# RC522.net
KiCad netlist of a schematic drawn in Altium Designer
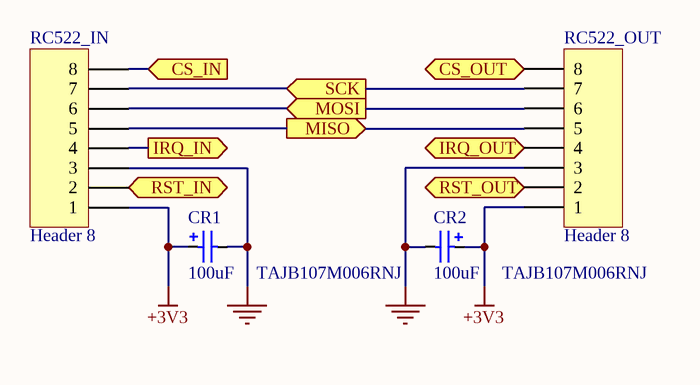
[diagram p0: RC522.SchDoc]

(export (version "E")
  (design (tool "Eeschema 10.0.6"))
  (components
    (comp (ref "CR1")
      (value "100uF     TAJB107M006RNJ")
      (footprint "CAP_TAN_B_3518")
      (description "Capacitor")
      (fields (field (name "Comment") "Cap_Tan"))
      (libsource (lib "Peace的集成库") (part "Cap_Tan"))
    )
    (comp (ref "CR2")
      (value "100uF     TAJB107M006RNJ")
      (footprint "CAP_TAN_B_3518")
      (description "Capacitor")
      (fields (field (name "Comment") "Cap_Tan"))
      (libsource (lib "Peace的集成库") (part "Cap_Tan"))
    )
    (comp (ref "RC522_IN")
      (value "Header 8")
      (footprint "HX2.54-8")
      (description "Header, 8-Pin")
      (fields (field (name "PUBLISHER") "Altium Limited"))
      (libsource (lib "") (part "Header 8_1"))
    )
    (comp (ref "RC522_OUT")
      (value "Header 8")
      (footprint "HX2.54-8")
      (description "Header, 8-Pin")
      (fields (field (name "PUBLISHER") "Altium Limited"))
      (libsource (lib "原理图库") (part "Header 8"))
    )
  )
  (nets
    (net (code "1") (name "+3V3") (class "Default")
      (node (ref "CR1") (pin "1") (pinfunction "1_1") (pintype "passive"))
      (node (ref "CR2") (pin "1") (pinfunction "1_1") (pintype "passive"))
      (node (ref "RC522_IN") (pin "1") (pinfunction "1_1") (pintype "passive"))
      (node (ref "RC522_OUT") (pin "1") (pinfunction "1_1") (pintype "passive"))
    )
    (net (code "2") (name "/CS_IN") (class "Default")
      (node (ref "RC522_IN") (pin "8") (pinfunction "8_8") (pintype "passive"))
    )
    (net (code "3") (name "/CS_OUT") (class "Default")
      (node (ref "RC522_OUT") (pin "8") (pinfunction "8_8") (pintype "passive"))
    )
    (net (code "4") (name "/IRQ_IN") (class "Default")
      (node (ref "RC522_IN") (pin "4") (pinfunction "4_4") (pintype "passive"))
    )
    (net (code "5") (name "/IRQ_OUT") (class "Default")
      (node (ref "RC522_OUT") (pin "4") (pinfunction "4_4") (pintype "passive"))
    )
    (net (code "6") (name "/MISO") (class "Default")
      (node (ref "RC522_IN") (pin "5") (pinfunction "5_5") (pintype "passive"))
      (node (ref "RC522_OUT") (pin "5") (pinfunction "5_5") (pintype "passive"))
    )
    (net (code "7") (name "/MOSI") (class "Default")
      (node (ref "RC522_IN") (pin "6") (pinfunction "6_6") (pintype "passive"))
      (node (ref "RC522_OUT") (pin "6") (pinfunction "6_6") (pintype "passive"))
    )
    (net (code "8") (name "/RST_IN") (class "Default")
      (node (ref "RC522_IN") (pin "2") (pinfunction "2_2") (pintype "passive"))
    )
    (net (code "9") (name "/RST_OUT") (class "Default")
      (node (ref "RC522_OUT") (pin "2") (pinfunction "2_2") (pintype "passive"))
    )
    (net (code "10") (name "/SCK") (class "Default")
      (node (ref "RC522_IN") (pin "7") (pinfunction "7_7") (pintype "passive"))
      (node (ref "RC522_OUT") (pin "7") (pinfunction "7_7") (pintype "passive"))
    )
    (net (code "11") (name "GND") (class "Default")
      (node (ref "CR1") (pin "2") (pinfunction "2_2") (pintype "passive"))
      (node (ref "CR2") (pin "2") (pinfunction "2_2") (pintype "passive"))
      (node (ref "RC522_IN") (pin "3") (pinfunction "3_3") (pintype "passive"))
      (node (ref "RC522_OUT") (pin "3") (pinfunction "3_3") (pintype "passive"))
    )
  )
)
